# Counter_60sec_THT.net
KiCad netlist of a schematic drawn in EAGLE
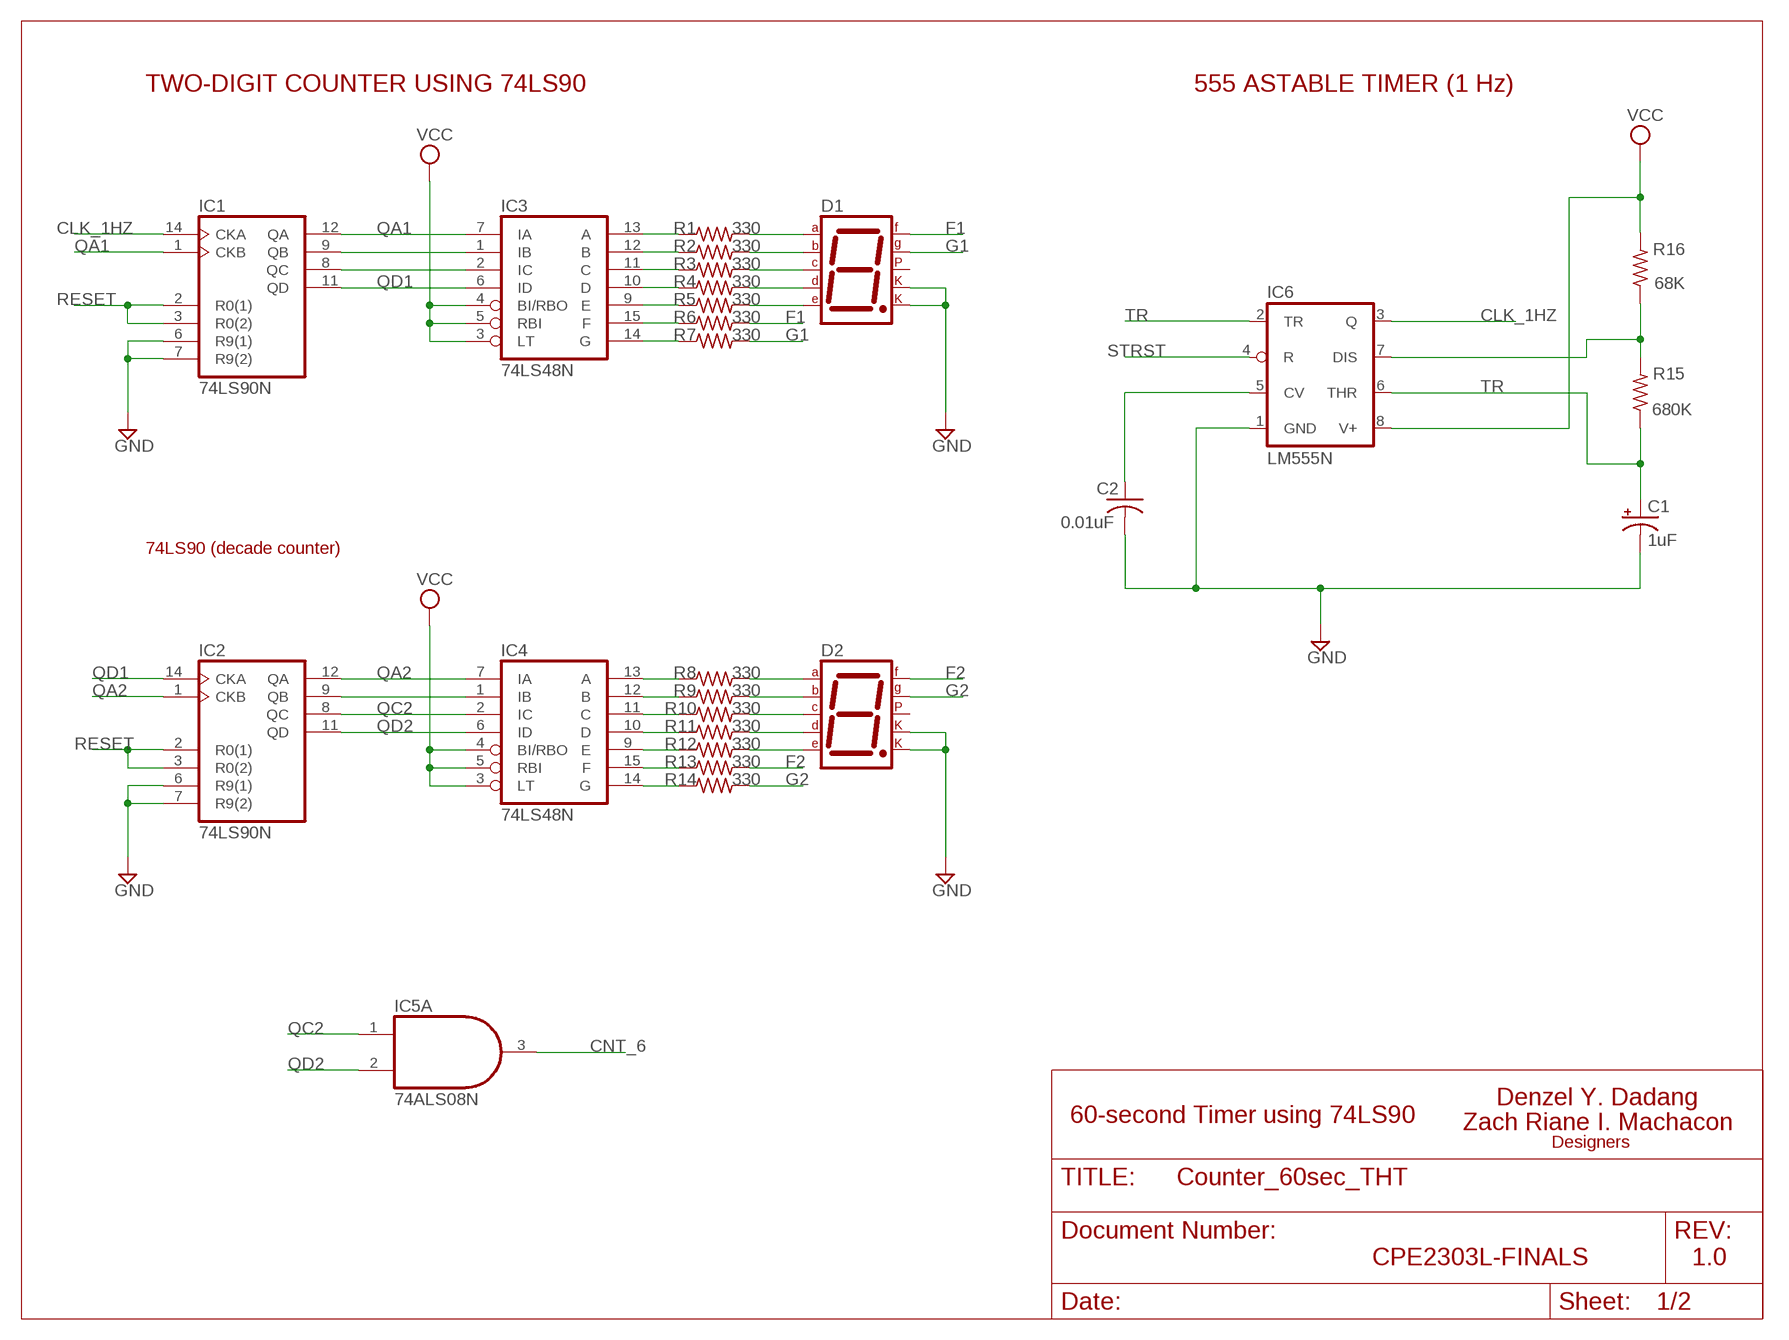
[diagram p0: schematic, sheet 1]
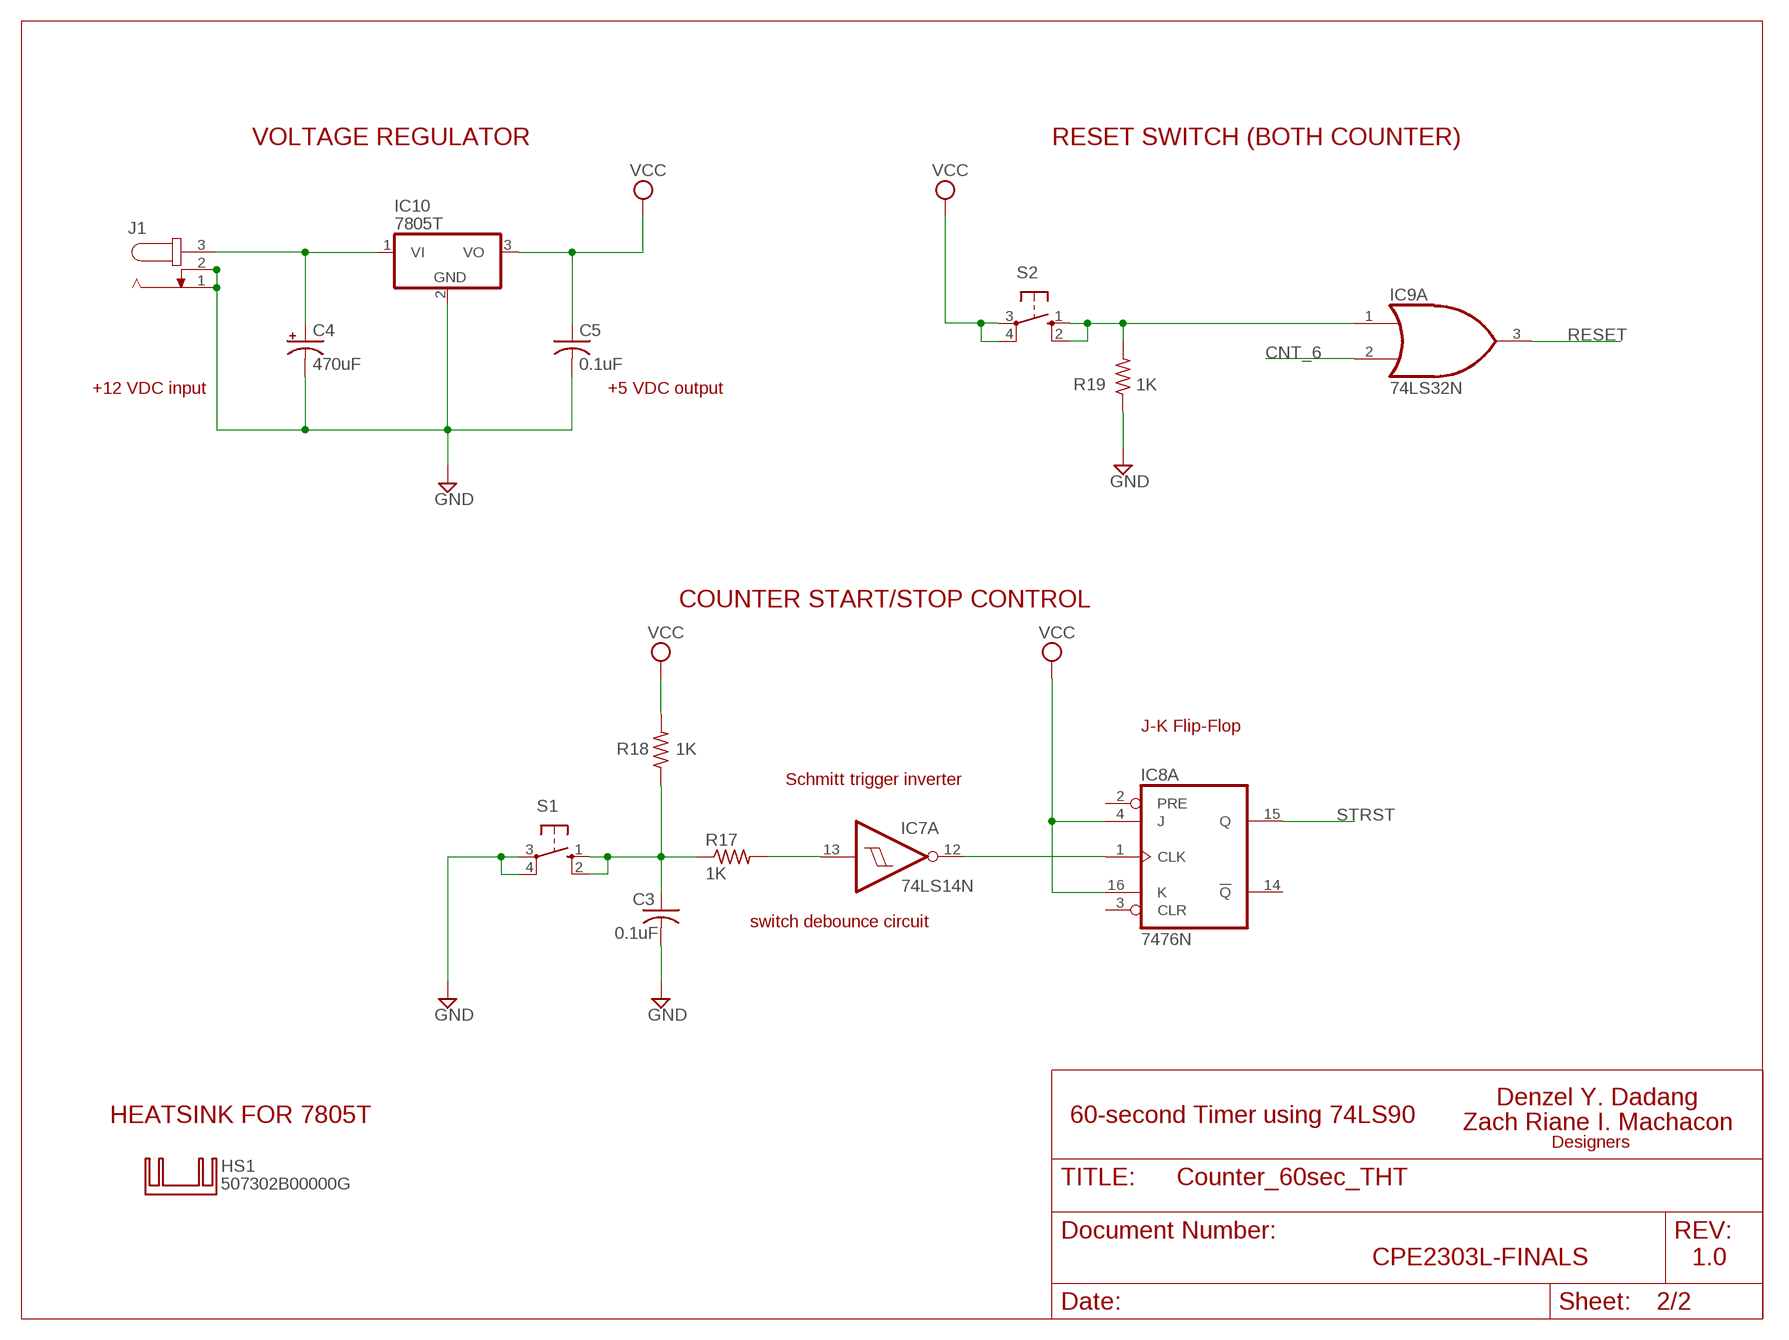
[diagram p1: schematic, sheet 2]

(export (version "E")
  (design (tool "Eeschema 10.0.6"))
  (components
    (comp (ref "C1")
      (value "1uF")
      (footprint "eagle-import:E1,8-4")
      (libsource (lib "eagle-import") (part "CPOL-USE1.8-4"))
    )
    (comp (ref "C2")
      (value "0.01uF")
      (footprint "eagle-import:C025-025X050")
      (libsource (lib "eagle-import") (part "C-US025-025X050"))
    )
    (comp (ref "D1")
      (value "7SEG-CK")
      (footprint "eagle-import:7SEG-13")
      (libsource (lib "eagle-import") (part "7SEG-CK"))
    )
    (comp (ref "D2")
      (value "7SEG-CK")
      (footprint "eagle-import:7SEG-13")
      (libsource (lib "eagle-import") (part "7SEG-CK"))
    )
    (comp (ref "IC1")
      (value "74LS90N")
      (footprint "eagle-import:DIL14")
      (libsource (lib "eagle-import") (part "7490NLS"))
    )
    (comp (ref "IC2")
      (value "74LS90N")
      (footprint "eagle-import:DIL14")
      (libsource (lib "eagle-import") (part "7490NLS"))
    )
    (comp (ref "IC3")
      (value "74LS48N")
      (footprint "eagle-import:DIL16")
      (libsource (lib "eagle-import") (part "7448NLS"))
    )
    (comp (ref "IC4")
      (value "74LS48N")
      (footprint "eagle-import:DIL16")
      (libsource (lib "eagle-import") (part "7448NLS"))
    )
    (comp (ref "IC5")
      (value "74ALS08N")
      (footprint "eagle-import:DIL14")
      (libsource (lib "eagle-import") (part "7408NALS"))
    )
    (comp (ref "IC6")
      (value "LM555N")
      (footprint "eagle-import:DIL08")
      (libsource (lib "eagle-import") (part "555NLM"))
    )
    (comp (ref "R1")
      (value "330")
      (footprint "eagle-import:0204_7")
      (libsource (lib "eagle-import") (part "R-US_0204/7"))
    )
    (comp (ref "R2")
      (value "330")
      (footprint "eagle-import:0204_7")
      (libsource (lib "eagle-import") (part "R-US_0204/7"))
    )
    (comp (ref "R3")
      (value "330")
      (footprint "eagle-import:0204_7")
      (libsource (lib "eagle-import") (part "R-US_0204/7"))
    )
    (comp (ref "R4")
      (value "330")
      (footprint "eagle-import:0204_7")
      (libsource (lib "eagle-import") (part "R-US_0204/7"))
    )
    (comp (ref "R5")
      (value "330")
      (footprint "eagle-import:0204_7")
      (libsource (lib "eagle-import") (part "R-US_0204/7"))
    )
    (comp (ref "R6")
      (value "330")
      (footprint "eagle-import:0204_7")
      (libsource (lib "eagle-import") (part "R-US_0204/7"))
    )
    (comp (ref "R7")
      (value "330")
      (footprint "eagle-import:0204_7")
      (libsource (lib "eagle-import") (part "R-US_0204/7"))
    )
    (comp (ref "R8")
      (value "330")
      (footprint "eagle-import:0204_7")
      (libsource (lib "eagle-import") (part "R-US_0204/7"))
    )
    (comp (ref "R9")
      (value "330")
      (footprint "eagle-import:0204_7")
      (libsource (lib "eagle-import") (part "R-US_0204/7"))
    )
    (comp (ref "R10")
      (value "330")
      (footprint "eagle-import:0204_7")
      (libsource (lib "eagle-import") (part "R-US_0204/7"))
    )
    (comp (ref "R11")
      (value "330")
      (footprint "eagle-import:0204_7")
      (libsource (lib "eagle-import") (part "R-US_0204/7"))
    )
    (comp (ref "R12")
      (value "330")
      (footprint "eagle-import:0204_7")
      (libsource (lib "eagle-import") (part "R-US_0204/7"))
    )
    (comp (ref "R13")
      (value "330")
      (footprint "eagle-import:0204_7")
      (libsource (lib "eagle-import") (part "R-US_0204/7"))
    )
    (comp (ref "R14")
      (value "330")
      (footprint "eagle-import:0204_7")
      (libsource (lib "eagle-import") (part "R-US_0204/7"))
    )
    (comp (ref "R15")
      (value "680K")
      (footprint "eagle-import:0204_7")
      (libsource (lib "eagle-import") (part "R-US_0204/7"))
    )
    (comp (ref "R16")
      (value "68K")
      (footprint "eagle-import:0204_7")
      (libsource (lib "eagle-import") (part "R-US_0204/7"))
    )
    (comp (ref "C3")
      (value "0.1uF")
      (footprint "eagle-import:C025-025X050")
      (libsource (lib "eagle-import") (part "C-US025-025X050"))
    )
    (comp (ref "C4")
      (value "470uF")
      (footprint "eagle-import:E1,8-4")
      (libsource (lib "eagle-import") (part "CPOL-USE1.8-4"))
    )
    (comp (ref "C5")
      (value "0.1uF")
      (footprint "eagle-import:C025-025X050")
      (libsource (lib "eagle-import") (part "C-US025-025X050"))
    )
    (comp (ref "HS1")
      (value "507302B00000G")
      (footprint "eagle-import:TO-220H")
      (libsource (lib "eagle-import") (part "507302B00000G"))
    )
    (comp (ref "IC7")
      (value "74LS14N")
      (footprint "eagle-import:DIL14")
      (libsource (lib "eagle-import") (part "7414NLS"))
    )
    (comp (ref "IC8")
      (value "7476N")
      (footprint "eagle-import:DIL16")
      (libsource (lib "eagle-import") (part "7476N"))
    )
    (comp (ref "IC9")
      (value "74LS32N")
      (footprint "eagle-import:DIL14")
      (libsource (lib "eagle-import") (part "7432NLS"))
    )
    (comp (ref "IC10")
      (value "7805T")
      (footprint "eagle-import:TO220H")
      (libsource (lib "eagle-import") (part "78T05"))
    )
    (comp (ref "J1")
      (value "JACK-PLUG1")
      (footprint "eagle-import:SPC4078")
      (libsource (lib "eagle-import") (part "JACK-PLUG1"))
    )
    (comp (ref "R17")
      (value "1K")
      (footprint "eagle-import:0204_7")
      (libsource (lib "eagle-import") (part "R-US_0204/7"))
    )
    (comp (ref "R18")
      (value "1K")
      (footprint "eagle-import:0204_7")
      (libsource (lib "eagle-import") (part "R-US_0204/7"))
    )
    (comp (ref "R19")
      (value "1K")
      (footprint "eagle-import:0204_7")
      (libsource (lib "eagle-import") (part "R-US_0204/7"))
    )
    (comp (ref "S1")
      (value "10-XX")
      (footprint "eagle-import:B3F-10XX")
      (fields (field (name "MPN") "B3F-1000"))
      (libsource (lib "eagle-import") (part "10-XX"))
    )
    (comp (ref "S2")
      (value "10-XX")
      (footprint "eagle-import:B3F-10XX")
      (fields (field (name "MPN") "B3F-1000"))
      (libsource (lib "eagle-import") (part "10-XX"))
    )
  )
  (nets
    (net (code "1") (name "CLK_1HZ") (class "Default")
      (node (ref "IC1") (pin "14") (pinfunction "CKA_14") (pintype "input"))
      (node (ref "IC6") (pin "3") (pinfunction "Q_3") (pintype "output"))
    )
    (net (code "2") (name "CNT_6") (class "Default")
      (node (ref "IC5") (pin "3") (pinfunction "O_3") (pintype "output"))
      (node (ref "IC9") (pin "2") (pinfunction "I1_2") (pintype "input"))
    )
    (net (code "3") (name "F1") (class "Default")
      (node (ref "D1") (pin "9") (pinfunction "F_9") (pintype "passive"))
      (node (ref "R6") (pin "2") (pinfunction "2_2") (pintype "passive"))
    )
    (net (code "4") (name "F2") (class "Default")
      (node (ref "D2") (pin "9") (pinfunction "F_9") (pintype "passive"))
      (node (ref "R13") (pin "2") (pinfunction "2_2") (pintype "passive"))
    )
    (net (code "5") (name "G1") (class "Default")
      (node (ref "D1") (pin "10") (pinfunction "G_10") (pintype "passive"))
      (node (ref "R7") (pin "2") (pinfunction "2_2") (pintype "passive"))
    )
    (net (code "6") (name "G2") (class "Default")
      (node (ref "D2") (pin "10") (pinfunction "G_10") (pintype "passive"))
      (node (ref "R14") (pin "2") (pinfunction "2_2") (pintype "passive"))
    )
    (net (code "7") (name "GND") (class "Default")
      (node (ref "C1") (pin "-") (pinfunction "-_-") (pintype "passive"))
      (node (ref "C2") (pin "2") (pinfunction "2_2") (pintype "passive"))
      (node (ref "C3") (pin "2") (pinfunction "2_2") (pintype "passive"))
      (node (ref "C4") (pin "-") (pinfunction "-_-") (pintype "passive"))
      (node (ref "C5") (pin "2") (pinfunction "2_2") (pintype "passive"))
      (node (ref "D1") (pin "3") (pinfunction "CK1_3") (pintype "passive"))
      (node (ref "D1") (pin "8") (pinfunction "CK2_8") (pintype "passive"))
      (node (ref "D2") (pin "3") (pinfunction "CK1_3") (pintype "passive"))
      (node (ref "D2") (pin "8") (pinfunction "CK2_8") (pintype "passive"))
      (node (ref "IC1") (pin "6") (pinfunction "R9(1)_6") (pintype "input"))
      (node (ref "IC1") (pin "7") (pinfunction "R9(2)_7") (pintype "input"))
      (node (ref "IC10") (pin "2") (pinfunction "GND_2") (pintype "passive"))
      (node (ref "IC2") (pin "6") (pinfunction "R9(1)_6") (pintype "input"))
      (node (ref "IC2") (pin "7") (pinfunction "R9(2)_7") (pintype "input"))
      (node (ref "IC6") (pin "1") (pinfunction "GND_1") (pintype "power_in"))
      (node (ref "J1") (pin "1") (pinfunction "1_1") (pintype "passive"))
      (node (ref "J1") (pin "2") (pinfunction "2_2") (pintype "passive"))
      (node (ref "R19") (pin "1") (pinfunction "1_1") (pintype "passive"))
      (node (ref "S1") (pin "3") (pinfunction "P_3") (pintype "passive"))
      (node (ref "S1") (pin "4") (pinfunction "P1_4") (pintype "passive"))
    )
    (net (code "8") (name "Net-(D1-A)") (class "Default")
      (node (ref "D1") (pin "7") (pinfunction "A_7") (pintype "passive"))
      (node (ref "R1") (pin "2") (pinfunction "2_2") (pintype "passive"))
    )
    (net (code "9") (name "Net-(D1-B)") (class "Default")
      (node (ref "D1") (pin "6") (pinfunction "B_6") (pintype "passive"))
      (node (ref "R2") (pin "2") (pinfunction "2_2") (pintype "passive"))
    )
    (net (code "10") (name "Net-(D1-C)") (class "Default")
      (node (ref "D1") (pin "4") (pinfunction "C_4") (pintype "passive"))
      (node (ref "R3") (pin "2") (pinfunction "2_2") (pintype "passive"))
    )
    (net (code "11") (name "Net-(D1-D)") (class "Default")
      (node (ref "D1") (pin "2") (pinfunction "D_2") (pintype "passive"))
      (node (ref "R4") (pin "2") (pinfunction "2_2") (pintype "passive"))
    )
    (net (code "12") (name "Net-(D1-E)") (class "Default")
      (node (ref "D1") (pin "1") (pinfunction "E_1") (pintype "passive"))
      (node (ref "R5") (pin "2") (pinfunction "2_2") (pintype "passive"))
    )
    (net (code "13") (name "Net-(D2-A)") (class "Default")
      (node (ref "D2") (pin "7") (pinfunction "A_7") (pintype "passive"))
      (node (ref "R8") (pin "2") (pinfunction "2_2") (pintype "passive"))
    )
    (net (code "14") (name "Net-(D2-B)") (class "Default")
      (node (ref "D2") (pin "6") (pinfunction "B_6") (pintype "passive"))
      (node (ref "R9") (pin "2") (pinfunction "2_2") (pintype "passive"))
    )
    (net (code "15") (name "Net-(D2-C)") (class "Default")
      (node (ref "D2") (pin "4") (pinfunction "C_4") (pintype "passive"))
      (node (ref "R10") (pin "2") (pinfunction "2_2") (pintype "passive"))
    )
    (net (code "16") (name "Net-(D2-D)") (class "Default")
      (node (ref "D2") (pin "2") (pinfunction "D_2") (pintype "passive"))
      (node (ref "R11") (pin "2") (pinfunction "2_2") (pintype "passive"))
    )
    (net (code "17") (name "Net-(D2-E)") (class "Default")
      (node (ref "D2") (pin "1") (pinfunction "E_1") (pintype "passive"))
      (node (ref "R12") (pin "2") (pinfunction "2_2") (pintype "passive"))
    )
    (net (code "18") (name "Net-(IC1A-QB)") (class "Default")
      (node (ref "IC1") (pin "9") (pinfunction "QB_9") (pintype "output"))
      (node (ref "IC3") (pin "1") (pinfunction "IB_1") (pintype "input"))
    )
    (net (code "19") (name "Net-(IC1A-QC)") (class "Default")
      (node (ref "IC1") (pin "8") (pinfunction "QC_8") (pintype "output"))
      (node (ref "IC3") (pin "2") (pinfunction "IC_2") (pintype "input"))
    )
    (net (code "20") (name "Net-(IC2A-QB)") (class "Default")
      (node (ref "IC2") (pin "9") (pinfunction "QB_9") (pintype "output"))
      (node (ref "IC4") (pin "1") (pinfunction "IB_1") (pintype "input"))
    )
    (net (code "21") (name "Net-(IC3A-A)") (class "Default")
      (node (ref "IC3") (pin "13") (pinfunction "A_13") (pintype "output"))
      (node (ref "R1") (pin "1") (pinfunction "1_1") (pintype "passive"))
    )
    (net (code "22") (name "Net-(IC3A-B)") (class "Default")
      (node (ref "IC3") (pin "12") (pinfunction "B_12") (pintype "output"))
      (node (ref "R2") (pin "1") (pinfunction "1_1") (pintype "passive"))
    )
    (net (code "23") (name "Net-(IC3A-C)") (class "Default")
      (node (ref "IC3") (pin "11") (pinfunction "C_11") (pintype "output"))
      (node (ref "R3") (pin "1") (pinfunction "1_1") (pintype "passive"))
    )
    (net (code "24") (name "Net-(IC3A-D)") (class "Default")
      (node (ref "IC3") (pin "10") (pinfunction "D_10") (pintype "output"))
      (node (ref "R4") (pin "1") (pinfunction "1_1") (pintype "passive"))
    )
    (net (code "25") (name "Net-(IC3A-E)") (class "Default")
      (node (ref "IC3") (pin "9") (pinfunction "E_9") (pintype "output"))
      (node (ref "R5") (pin "1") (pinfunction "1_1") (pintype "passive"))
    )
    (net (code "26") (name "Net-(IC3A-F)") (class "Default")
      (node (ref "IC3") (pin "15") (pinfunction "F_15") (pintype "output"))
      (node (ref "R6") (pin "1") (pinfunction "1_1") (pintype "passive"))
    )
    (net (code "27") (name "Net-(IC3A-G)") (class "Default")
      (node (ref "IC3") (pin "14") (pinfunction "G_14") (pintype "output"))
      (node (ref "R7") (pin "1") (pinfunction "1_1") (pintype "passive"))
    )
    (net (code "28") (name "Net-(IC4A-A)") (class "Default")
      (node (ref "IC4") (pin "13") (pinfunction "A_13") (pintype "output"))
      (node (ref "R8") (pin "1") (pinfunction "1_1") (pintype "passive"))
    )
    (net (code "29") (name "Net-(IC4A-B)") (class "Default")
      (node (ref "IC4") (pin "12") (pinfunction "B_12") (pintype "output"))
      (node (ref "R9") (pin "1") (pinfunction "1_1") (pintype "passive"))
    )
    (net (code "30") (name "Net-(IC4A-C)") (class "Default")
      (node (ref "IC4") (pin "11") (pinfunction "C_11") (pintype "output"))
      (node (ref "R10") (pin "1") (pinfunction "1_1") (pintype "passive"))
    )
    (net (code "31") (name "Net-(IC4A-D)") (class "Default")
      (node (ref "IC4") (pin "10") (pinfunction "D_10") (pintype "output"))
      (node (ref "R11") (pin "1") (pinfunction "1_1") (pintype "passive"))
    )
    (net (code "32") (name "Net-(IC4A-E)") (class "Default")
      (node (ref "IC4") (pin "9") (pinfunction "E_9") (pintype "output"))
      (node (ref "R12") (pin "1") (pinfunction "1_1") (pintype "passive"))
    )
    (net (code "33") (name "Net-(IC4A-F)") (class "Default")
      (node (ref "IC4") (pin "15") (pinfunction "F_15") (pintype "output"))
      (node (ref "R13") (pin "1") (pinfunction "1_1") (pintype "passive"))
    )
    (net (code "34") (name "Net-(IC4A-G)") (class "Default")
      (node (ref "IC4") (pin "14") (pinfunction "G_14") (pintype "output"))
      (node (ref "R14") (pin "1") (pinfunction "1_1") (pintype "passive"))
    )
    (net (code "35") (name "Net-(IC6-CV)") (class "Default")
      (node (ref "C2") (pin "1") (pinfunction "1_1") (pintype "passive"))
      (node (ref "IC6") (pin "5") (pinfunction "CV_5") (pintype "input"))
    )
    (net (code "36") (name "Net-(IC6-DIS)") (class "Default")
      (node (ref "IC6") (pin "7") (pinfunction "DIS_7") (pintype "input"))
      (node (ref "R15") (pin "2") (pinfunction "2_2") (pintype "passive"))
      (node (ref "R16") (pin "1") (pinfunction "1_1") (pintype "passive"))
    )
    (net (code "37") (name "Net-(IC7A-I)") (class "Default")
      (node (ref "IC7") (pin "13") (pinfunction "I_13") (pintype "input"))
      (node (ref "R17") (pin "2") (pinfunction "2_2") (pintype "passive"))
    )
    (net (code "38") (name "Net-(IC7A-O)") (class "Default")
      (node (ref "IC7") (pin "12") (pinfunction "O_12") (pintype "output"))
      (node (ref "IC8") (pin "1") (pinfunction "CLK_1") (pintype "input"))
    )
    (net (code "39") (name "Net-(IC9A-I0)") (class "Default")
      (node (ref "IC9") (pin "1") (pinfunction "I0_1") (pintype "input"))
      (node (ref "R19") (pin "2") (pinfunction "2_2") (pintype "passive"))
      (node (ref "S2") (pin "1") (pinfunction "S_1") (pintype "passive"))
      (node (ref "S2") (pin "2") (pinfunction "S1_2") (pintype "passive"))
    )
    (net (code "40") (name "Net-(IC10-VI)") (class "Default")
      (node (ref "C4") (pin "+") (pinfunction "+_+") (pintype "passive"))
      (node (ref "IC10") (pin "1") (pinfunction "VI_1") (pintype "input"))
      (node (ref "J1") (pin "3") (pinfunction "3_3") (pintype "passive"))
    )
    (net (code "41") (name "Net-(S1-S)") (class "Default")
      (node (ref "C3") (pin "1") (pinfunction "1_1") (pintype "passive"))
      (node (ref "R17") (pin "1") (pinfunction "1_1") (pintype "passive"))
      (node (ref "R18") (pin "1") (pinfunction "1_1") (pintype "passive"))
      (node (ref "S1") (pin "1") (pinfunction "S_1") (pintype "passive"))
      (node (ref "S1") (pin "2") (pinfunction "S1_2") (pintype "passive"))
    )
    (net (code "42") (name "QA1") (class "Default")
      (node (ref "IC1") (pin "1") (pinfunction "CKB_1") (pintype "input"))
      (node (ref "IC1") (pin "12") (pinfunction "QA_12") (pintype "output"))
      (node (ref "IC3") (pin "7") (pinfunction "IA_7") (pintype "input"))
    )
    (net (code "43") (name "QA2") (class "Default")
      (node (ref "IC2") (pin "1") (pinfunction "CKB_1") (pintype "input"))
      (node (ref "IC2") (pin "12") (pinfunction "QA_12") (pintype "output"))
      (node (ref "IC4") (pin "7") (pinfunction "IA_7") (pintype "input"))
    )
    (net (code "44") (name "QC2") (class "Default")
      (node (ref "IC2") (pin "8") (pinfunction "QC_8") (pintype "output"))
      (node (ref "IC4") (pin "2") (pinfunction "IC_2") (pintype "input"))
      (node (ref "IC5") (pin "1") (pinfunction "I0_1") (pintype "input"))
    )
    (net (code "45") (name "QD1") (class "Default")
      (node (ref "IC1") (pin "11") (pinfunction "QD_11") (pintype "output"))
      (node (ref "IC2") (pin "14") (pinfunction "CKA_14") (pintype "input"))
      (node (ref "IC3") (pin "6") (pinfunction "ID_6") (pintype "input"))
    )
    (net (code "46") (name "QD2") (class "Default")
      (node (ref "IC2") (pin "11") (pinfunction "QD_11") (pintype "output"))
      (node (ref "IC4") (pin "6") (pinfunction "ID_6") (pintype "input"))
      (node (ref "IC5") (pin "2") (pinfunction "I1_2") (pintype "input"))
    )
    (net (code "47") (name "RESET") (class "Default")
      (node (ref "IC1") (pin "2") (pinfunction "R0(1)_2") (pintype "input"))
      (node (ref "IC1") (pin "3") (pinfunction "R0(2)_3") (pintype "input"))
      (node (ref "IC2") (pin "2") (pinfunction "R0(1)_2") (pintype "input"))
      (node (ref "IC2") (pin "3") (pinfunction "R0(2)_3") (pintype "input"))
      (node (ref "IC9") (pin "3") (pinfunction "O_3") (pintype "output"))
    )
    (net (code "48") (name "STRST") (class "Default")
      (node (ref "IC6") (pin "4") (pinfunction "R_4") (pintype "input"))
      (node (ref "IC8") (pin "15") (pinfunction "Q_15") (pintype "output"))
    )
    (net (code "49") (name "TR") (class "Default")
      (node (ref "C1") (pin "+") (pinfunction "+_+") (pintype "passive"))
      (node (ref "IC6") (pin "2") (pinfunction "TR_2") (pintype "input"))
      (node (ref "IC6") (pin "6") (pinfunction "THR_6") (pintype "input"))
      (node (ref "R15") (pin "1") (pinfunction "1_1") (pintype "passive"))
    )
    (net (code "50") (name "VCC") (class "Default")
      (node (ref "C5") (pin "1") (pinfunction "1_1") (pintype "passive"))
      (node (ref "IC10") (pin "3") (pinfunction "VO_3") (pintype "passive"))
      (node (ref "IC3") (pin "3") (pinfunction "LT_3") (pintype "input"))
      (node (ref "IC3") (pin "4") (pinfunction "BI/RBO_4") (pintype "input"))
      (node (ref "IC3") (pin "5") (pinfunction "RBI_5") (pintype "input"))
      (node (ref "IC4") (pin "3") (pinfunction "LT_3") (pintype "input"))
      (node (ref "IC4") (pin "4") (pinfunction "BI/RBO_4") (pintype "input"))
      (node (ref "IC4") (pin "5") (pinfunction "RBI_5") (pintype "input"))
      (node (ref "IC6") (pin "8") (pinfunction "V+_8") (pintype "power_in"))
      (node (ref "IC8") (pin "16") (pinfunction "K_16") (pintype "input"))
      (node (ref "IC8") (pin "4") (pinfunction "J_4") (pintype "input"))
      (node (ref "R16") (pin "2") (pinfunction "2_2") (pintype "passive"))
      (node (ref "R18") (pin "2") (pinfunction "2_2") (pintype "passive"))
      (node (ref "S2") (pin "3") (pinfunction "P_3") (pintype "passive"))
      (node (ref "S2") (pin "4") (pinfunction "P1_4") (pintype "passive"))
    )
    (net (code "51") (name "unconnected-(D1-DP-Pad5)") (class "Default")
      (node (ref "D1") (pin "5") (pinfunction "DP_5") (pintype "passive"))
    )
    (net (code "52") (name "unconnected-(D2-DP-Pad5)") (class "Default")
      (node (ref "D2") (pin "5") (pinfunction "DP_5") (pintype "passive"))
    )
    (net (code "53") (name "unconnected-(IC8A-CLR-Pad3)") (class "Default")
      (node (ref "IC8") (pin "3") (pinfunction "CLR_3") (pintype "input"))
    )
    (net (code "54") (name "unconnected-(IC8A-PRE-Pad2)") (class "Default")
      (node (ref "IC8") (pin "2") (pinfunction "PRE_2") (pintype "input"))
    )
    (net (code "55") (name "unconnected-(IC8A-~{Q}-Pad14)") (class "Default")
      (node (ref "IC8") (pin "14") (pinfunction "~{Q}_14") (pintype "output"))
    )
  )
)
